# mainboard.net
KiCad netlist of a schematic drawn in Altium Designer
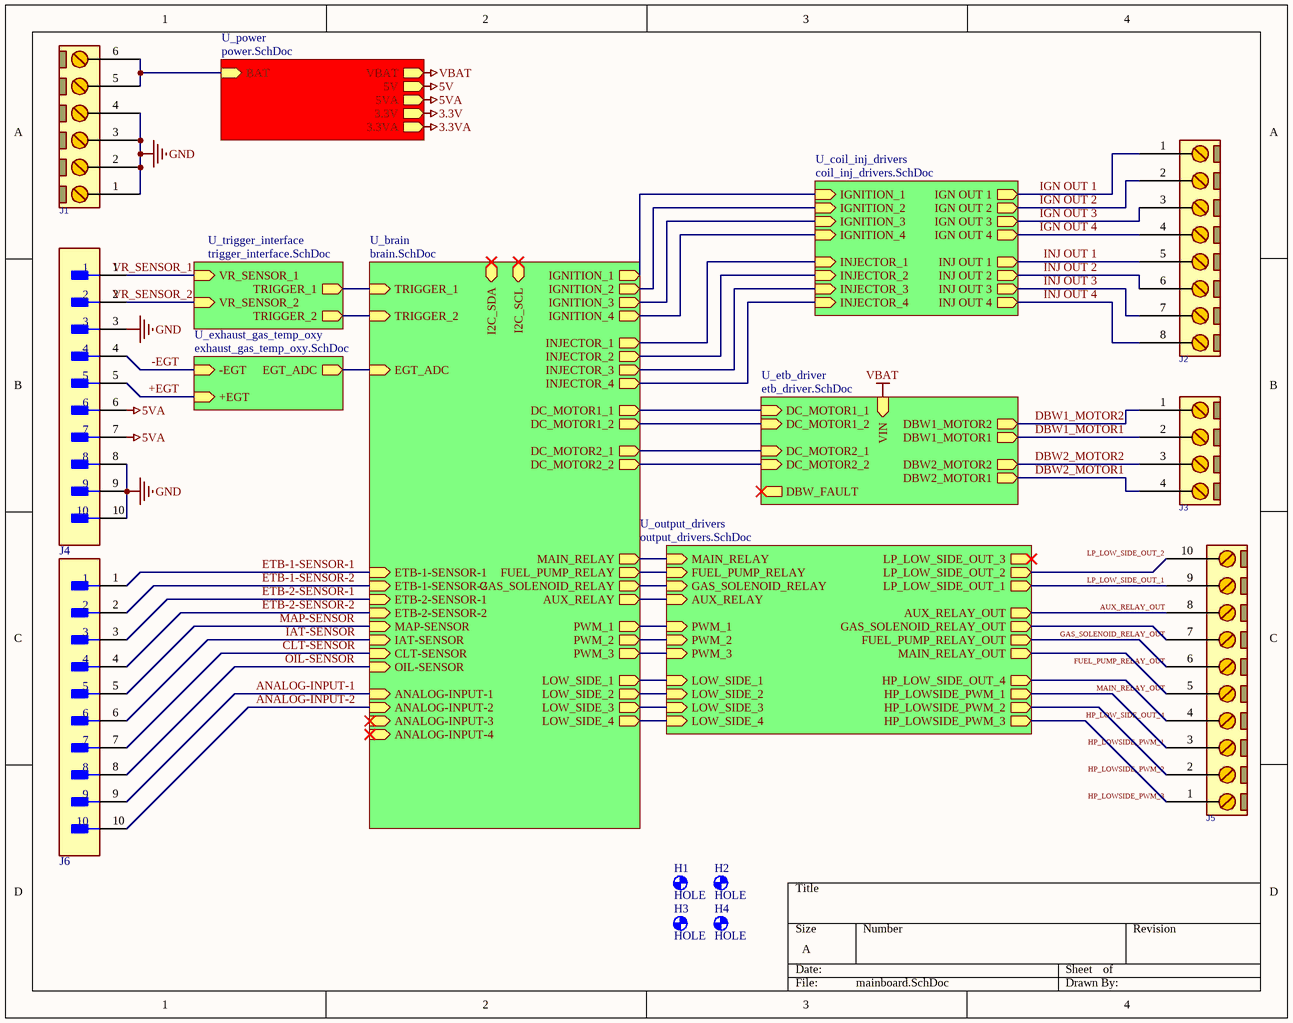
[diagram p0: mainboard.SchDoc]

(export (version "E")
  (design (tool "Eeschema 10.0.6"))
  (components
    (comp (ref "H1")
      (value "HOLE")
      (footprint "P3.2")
      (description "MOUNTING HOLE with drill center marker")
      (libsource (lib "alib") (part "MOUNT-HOLE"))
    )
    (comp (ref "H2")
      (value "HOLE")
      (footprint "P3.2")
      (description "MOUNTING HOLE with drill center marker")
      (libsource (lib "alib") (part "MOUNT-HOLE"))
    )
    (comp (ref "H3")
      (value "HOLE")
      (footprint "P3.2")
      (description "MOUNTING HOLE with drill center marker")
      (libsource (lib "alib") (part "MOUNT-HOLE"))
    )
    (comp (ref "H4")
      (value "HOLE")
      (footprint "P3.2")
      (description "MOUNTING HOLE with drill center marker")
      (libsource (lib "alib") (part "MOUNT-HOLE"))
    )
    (comp (ref "J1")
      (value "CONN_TB6")
      (footprint "MSTB_6")
      (description "CONN, PHOENIX MSTB, 5-G, 5.08mm pitch")
      (libsource (lib "conn_terminalB") (part "CONN_MSTB_6"))
    )
    (comp (ref "J2")
      (value "CONN_TB8")
      (footprint "MSTB_8")
      (description "CONN, PHOENIX MSTB, 5-G, 5.08mm pitch")
      (libsource (lib "conn_terminalB") (part "CONN_MSTB_8"))
    )
    (comp (ref "J3")
      (value "CONN_TB4")
      (footprint "MSTB_4")
      (description "CONN, PHOENIX MSTB, 5-G, 5.08mm pitch")
      (libsource (lib "conn_terminalB") (part "CONN_MSTB_4"))
    )
    (comp (ref "J4")
      (value "PHOENIX MINI 10P")
      (footprint "CON_PHOENIX_MINI_10")
      (description "1803358 Header; 8 A; 160 V; 3.81; 10; Soldering; 1.2 mm; 2.5 kV; 160/250 V; PBT")
      (fields (field (name "VOLTAGE") "300V"))
      (libsource (lib "alib") (part "PHOENIX MINI 10P"))
    )
    (comp (ref "J5")
      (value "CONN_TB10")
      (footprint "MSTB_10")
      (description "CONN, PHOENIX MSTB, 5-G, 5.08mm pitch")
      (libsource (lib "conn_terminalB") (part "CONN_MSTB_10"))
    )
    (comp (ref "J6")
      (value "PHOENIX MINI 10P")
      (footprint "CON_PHOENIX_MINI_10")
      (description "1803358 Header; 8 A; 160 V; 3.81; 10; Soldering; 1.2 mm; 2.5 kV; 160/250 V; PBT")
      (fields (field (name "VOLTAGE") "300V"))
      (libsource (lib "alib") (part "PHOENIX MINI 10P"))
    )
  )
  (nets
    (net (code "1") (name "/+EGT") (class "Default")
      (node (ref "J4") (pin "5") (pinfunction "5_5") (pintype "passive"))
    )
    (net (code "2") (name "/-EGT") (class "Default")
      (node (ref "J4") (pin "4") (pinfunction "4_4") (pintype "passive"))
    )
    (net (code "3") (name "/ANALOG-INPUT-1") (class "Default")
      (node (ref "J6") (pin "9") (pinfunction "9_9") (pintype "passive"))
    )
    (net (code "4") (name "/ANALOG-INPUT-2") (class "Default")
      (node (ref "J6") (pin "10") (pinfunction "10_10") (pintype "passive"))
    )
    (net (code "8") (name "/AUX_RELAY_OUT") (class "Default")
      (node (ref "J5") (pin "8") (pinfunction "8_8") (pintype "passive"))
    )
    (net (code "9") (name "/BAT") (class "Default")
      (node (ref "J1") (pin "5") (pinfunction "5_5") (pintype "passive"))
      (node (ref "J1") (pin "6") (pinfunction "6_6") (pintype "passive"))
    )
    (net (code "10") (name "/CLT-SENSOR") (class "Default")
      (node (ref "J6") (pin "7") (pinfunction "7_7") (pintype "passive"))
    )
    (net (code "11") (name "/DBW1_MOTOR1") (class "Default")
      (node (ref "J3") (pin "2") (pinfunction "2_2") (pintype "passive"))
    )
    (net (code "12") (name "/DBW1_MOTOR2") (class "Default")
      (node (ref "J3") (pin "1") (pinfunction "1_1") (pintype "passive"))
    )
    (net (code "13") (name "/DBW2_MOTOR1") (class "Default")
      (node (ref "J3") (pin "4") (pinfunction "4_4") (pintype "passive"))
    )
    (net (code "14") (name "/DBW2_MOTOR2") (class "Default")
      (node (ref "J3") (pin "3") (pinfunction "3_3") (pintype "passive"))
    )
    (net (code "21") (name "/ETB-1-SENSOR-1") (class "Default")
      (node (ref "J6") (pin "1") (pinfunction "1_1") (pintype "passive"))
    )
    (net (code "22") (name "/ETB-1-SENSOR-2") (class "Default")
      (node (ref "J6") (pin "2") (pinfunction "2_2") (pintype "passive"))
    )
    (net (code "23") (name "/ETB-2-SENSOR-1") (class "Default")
      (node (ref "J6") (pin "3") (pinfunction "3_3") (pintype "passive"))
    )
    (net (code "24") (name "/ETB-2-SENSOR-2") (class "Default")
      (node (ref "J6") (pin "4") (pinfunction "4_4") (pintype "passive"))
    )
    (net (code "26") (name "/FUEL_PUMP_RELAY_OUT") (class "Default")
      (node (ref "J5") (pin "6") (pinfunction "6_6") (pintype "passive"))
    )
    (net (code "28") (name "/GAS_SOLENOID_RELAY_OUT") (class "Default")
      (node (ref "J5") (pin "7") (pinfunction "7_7") (pintype "passive"))
    )
    (net (code "29") (name "/HP_LOWSIDE_PWM_1") (class "Default")
      (node (ref "J5") (pin "3") (pinfunction "3_3") (pintype "passive"))
    )
    (net (code "30") (name "/HP_LOWSIDE_PWM_2") (class "Default")
      (node (ref "J5") (pin "2") (pinfunction "2_2") (pintype "passive"))
    )
    (net (code "31") (name "/HP_LOWSIDE_PWM_3") (class "Default")
      (node (ref "J5") (pin "1") (pinfunction "1_1") (pintype "passive"))
    )
    (net (code "32") (name "/HP_LOW_SIDE_OUT_4") (class "Default")
      (node (ref "J5") (pin "4") (pinfunction "4_4") (pintype "passive"))
    )
    (net (code "35") (name "/IAT-SENSOR") (class "Default")
      (node (ref "J6") (pin "6") (pinfunction "6_6") (pintype "passive"))
    )
    (net (code "36") (name "/IGN OUT 1") (class "Default")
      (node (ref "J2") (pin "1") (pinfunction "1_1") (pintype "passive"))
    )
    (net (code "37") (name "/IGN OUT 2") (class "Default")
      (node (ref "J2") (pin "2") (pinfunction "2_2") (pintype "passive"))
    )
    (net (code "38") (name "/IGN OUT 3") (class "Default")
      (node (ref "J2") (pin "3") (pinfunction "3_3") (pintype "passive"))
    )
    (net (code "39") (name "/IGN OUT 4") (class "Default")
      (node (ref "J2") (pin "4") (pinfunction "4_4") (pintype "passive"))
    )
    (net (code "44") (name "/INJ OUT 1") (class "Default")
      (node (ref "J2") (pin "5") (pinfunction "5_5") (pintype "passive"))
    )
    (net (code "45") (name "/INJ OUT 2") (class "Default")
      (node (ref "J2") (pin "6") (pinfunction "6_6") (pintype "passive"))
    )
    (net (code "46") (name "/INJ OUT 3") (class "Default")
      (node (ref "J2") (pin "7") (pinfunction "7_7") (pintype "passive"))
    )
    (net (code "47") (name "/INJ OUT 4") (class "Default")
      (node (ref "J2") (pin "8") (pinfunction "8_8") (pintype "passive"))
    )
    (net (code "56") (name "/LP_LOW_SIDE_OUT_1") (class "Default")
      (node (ref "J5") (pin "9") (pinfunction "9_9") (pintype "passive"))
    )
    (net (code "57") (name "/LP_LOW_SIDE_OUT_2") (class "Default")
      (node (ref "J5") (pin "10") (pinfunction "10_10") (pintype "passive"))
    )
    (net (code "60") (name "/MAIN_RELAY_OUT") (class "Default")
      (node (ref "J5") (pin "5") (pinfunction "5_5") (pintype "passive"))
    )
    (net (code "61") (name "/MAP-SENSOR") (class "Default")
      (node (ref "J6") (pin "5") (pinfunction "5_5") (pintype "passive"))
    )
    (net (code "62") (name "/OIL-SENSOR") (class "Default")
      (node (ref "J6") (pin "8") (pinfunction "8_8") (pintype "passive"))
    )
    (net (code "68") (name "/VR_SENSOR_1") (class "Default")
      (node (ref "J4") (pin "1") (pinfunction "1_1") (pintype "passive"))
    )
    (net (code "69") (name "/VR_SENSOR_2") (class "Default")
      (node (ref "J4") (pin "2") (pinfunction "2_2") (pintype "passive"))
    )
    (net (code "73") (name "5VA") (class "Default")
      (node (ref "J4") (pin "6") (pinfunction "6_6") (pintype "passive"))
      (node (ref "J4") (pin "7") (pinfunction "7_7") (pintype "passive"))
    )
    (net (code "74") (name "GND") (class "Default")
      (node (ref "J1") (pin "1") (pinfunction "1_1") (pintype "passive"))
      (node (ref "J1") (pin "2") (pinfunction "2_2") (pintype "passive"))
      (node (ref "J1") (pin "3") (pinfunction "3_3") (pintype "passive"))
      (node (ref "J1") (pin "4") (pinfunction "4_4") (pintype "passive"))
      (node (ref "J4") (pin "10") (pinfunction "10_10") (pintype "passive"))
      (node (ref "J4") (pin "3") (pinfunction "3_3") (pintype "passive"))
      (node (ref "J4") (pin "8") (pinfunction "8_8") (pintype "passive"))
      (node (ref "J4") (pin "9") (pinfunction "9_9") (pintype "passive"))
    )
  )
)
